# Sparkfun_MiP_ProMini-Pack.net
KiCad netlist of a schematic drawn in EAGLE
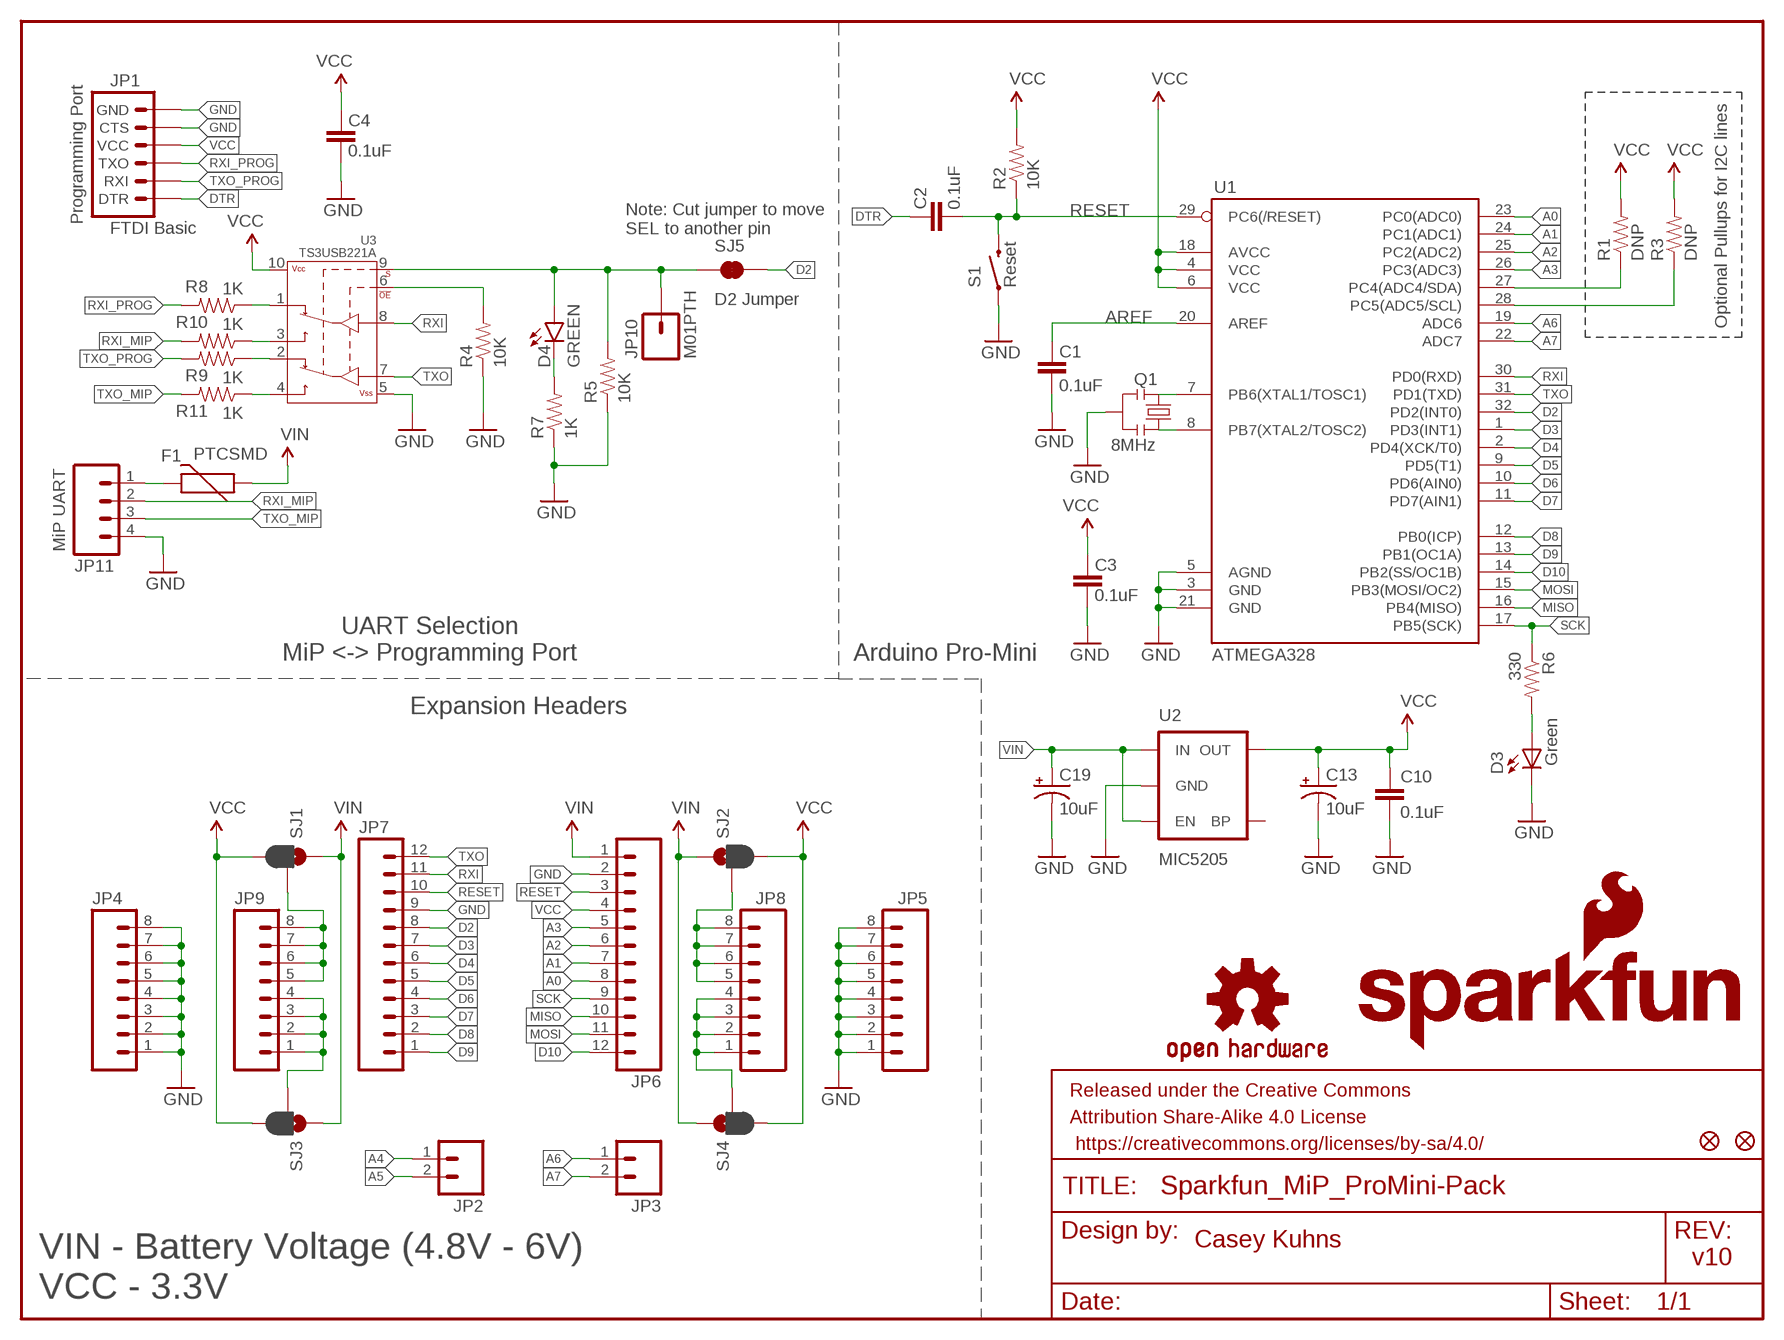
[diagram p0: schematic, sheet 1]

(export (version "E")
  (design (tool "Eeschema 10.0.6"))
  (components
    (comp (ref "C1")
      (value "0.1uF")
      (footprint "eagle-import:0603-CAP")
      (libsource (lib "eagle-import") (part "CAP0603-CAP"))
    )
    (comp (ref "C2")
      (value "0.1uF")
      (footprint "eagle-import:0603-CAP")
      (libsource (lib "eagle-import") (part "CAP0603-CAP"))
    )
    (comp (ref "C3")
      (value "0.1uF")
      (footprint "eagle-import:0603-CAP")
      (libsource (lib "eagle-import") (part "CAP0603-CAP"))
    )
    (comp (ref "C4")
      (value "0.1uF")
      (footprint "eagle-import:0603-CAP")
      (libsource (lib "eagle-import") (part "CAP0603-CAP"))
    )
    (comp (ref "C10")
      (value "0.1uF")
      (footprint "eagle-import:0603-CAP")
      (libsource (lib "eagle-import") (part "CAP0603-CAP"))
    )
    (comp (ref "C13")
      (value "10uF")
      (footprint "eagle-import:EIA3216")
      (libsource (lib "eagle-import") (part "CAP_POL1206"))
    )
    (comp (ref "C19")
      (value "10uF")
      (footprint "eagle-import:EIA3216")
      (libsource (lib "eagle-import") (part "CAP_POL1206"))
    )
    (comp (ref "D3")
      (value "Green")
      (footprint "eagle-import:0603-LED-ALT1")
      (libsource (lib "eagle-import") (part "LED"))
    )
    (comp (ref "D4")
      (value "GREEN")
      (footprint "eagle-import:LED-0603")
      (libsource (lib "eagle-import") (part "LED-GREEN0603"))
    )
    (comp (ref "F1")
      (value "PTCSMD")
      (footprint "eagle-import:PTC-1206")
      (libsource (lib "eagle-import") (part "PTCSMD"))
    )
    (comp (ref "FID1")
      (value "FIDUCIAL1X2")
      (footprint "eagle-import:FIDUCIAL-1X2")
      (libsource (lib "eagle-import") (part "FIDUCIAL1X2"))
    )
    (comp (ref "FID2")
      (value "FIDUCIAL1X2")
      (footprint "eagle-import:FIDUCIAL-1X2")
      (libsource (lib "eagle-import") (part "FIDUCIAL1X2"))
    )
    (comp (ref "FRAME1")
      (value "FRAME-LETTER")
      (footprint "eagle-import:CREATIVE_COMMONS")
      (libsource (lib "eagle-import") (part "FRAME-LETTER"))
    )
    (comp (ref "JP1")
      (value "FTDI Basic")
      (footprint "eagle-import:1X06")
      (libsource (lib "eagle-import") (part "ARDUINO_SERIAL_PROGRAMPTH"))
    )
    (comp (ref "JP2")
      (value "M02PTH")
      (footprint "eagle-import:1X02")
      (libsource (lib "eagle-import") (part "M02PTH"))
    )
    (comp (ref "JP3")
      (value "M02PTH")
      (footprint "eagle-import:1X02")
      (libsource (lib "eagle-import") (part "M02PTH"))
    )
    (comp (ref "JP4")
      (value "M081X08")
      (footprint "eagle-import:1X08")
      (libsource (lib "eagle-import") (part "M081X08"))
    )
    (comp (ref "JP5")
      (value "M081X08")
      (footprint "eagle-import:1X08")
      (libsource (lib "eagle-import") (part "M081X08"))
    )
    (comp (ref "JP6")
      (value "M12PTH")
      (footprint "eagle-import:1X12")
      (libsource (lib "eagle-import") (part "M12PTH"))
    )
    (comp (ref "JP7")
      (value "M12PTH")
      (footprint "eagle-import:1X12")
      (libsource (lib "eagle-import") (part "M12PTH"))
    )
    (comp (ref "JP8")
      (value "M081X08")
      (footprint "eagle-import:1X08")
      (libsource (lib "eagle-import") (part "M081X08"))
    )
    (comp (ref "JP9")
      (value "M081X08")
      (footprint "eagle-import:1X08")
      (libsource (lib "eagle-import") (part "M081X08"))
    )
    (comp (ref "JP10")
      (value "M01PTH")
      (footprint "eagle-import:1X01")
      (libsource (lib "eagle-import") (part "M01PTH"))
    )
    (comp (ref "JP11")
      (value "M04JST")
      (footprint "eagle-import:1X04-1.5MM_JST")
      (libsource (lib "eagle-import") (part "M04JST"))
    )
    (comp (ref "LOGO1")
      (value "SFE_LOGO_NAME_FLAME.1_INCH")
      (footprint "eagle-import:SFE_LOGO_NAME_FLAME_.1")
      (libsource (lib "eagle-import") (part "SFE_LOGO_NAME_FLAME.1_INCH"))
    )
    (comp (ref "LOGO2")
      (value "OSHW-LOGOS")
      (footprint "eagle-import:OSHW-LOGO-S")
      (libsource (lib "eagle-import") (part "OSHW-LOGOS"))
    )
    (comp (ref "Q1")
      (value "8MHz")
      (footprint "eagle-import:RESONATOR-SMD")
      (libsource (lib "eagle-import") (part "RESONATOR8MHZ"))
    )
    (comp (ref "R1")
      (value "DNP")
      (footprint "eagle-import:0603-RES")
      (libsource (lib "eagle-import") (part "RESISTOR0603-RES"))
    )
    (comp (ref "R2")
      (value "10K")
      (footprint "eagle-import:0603-RES")
      (libsource (lib "eagle-import") (part "RESISTOR0603-RES"))
    )
    (comp (ref "R3")
      (value "DNP")
      (footprint "eagle-import:0603-RES")
      (libsource (lib "eagle-import") (part "RESISTOR0603-RES"))
    )
    (comp (ref "R4")
      (value "10K")
      (footprint "eagle-import:0603-RES")
      (libsource (lib "eagle-import") (part "10KOHM1/10W1%(0603)0603"))
    )
    (comp (ref "R5")
      (value "10K")
      (footprint "eagle-import:0603-RES")
      (libsource (lib "eagle-import") (part "10KOHM1/10W1%(0603)0603"))
    )
    (comp (ref "R6")
      (value "330")
      (footprint "eagle-import:0603-RES")
      (libsource (lib "eagle-import") (part "RESISTOR0603-RES"))
    )
    (comp (ref "R7")
      (value "1K")
      (footprint "eagle-import:0603-RES")
      (libsource (lib "eagle-import") (part "1KOHM1/10W1%(0603)"))
    )
    (comp (ref "R8")
      (value "1K")
      (footprint "eagle-import:0603-RES")
      (libsource (lib "eagle-import") (part "1KOHM1/10W1%(0603)"))
    )
    (comp (ref "R9")
      (value "1K")
      (footprint "eagle-import:0603-RES")
      (libsource (lib "eagle-import") (part "1KOHM1/10W1%(0603)"))
    )
    (comp (ref "R10")
      (value "1K")
      (footprint "eagle-import:0603-RES")
      (libsource (lib "eagle-import") (part "1KOHM1/10W1%(0603)"))
    )
    (comp (ref "R11")
      (value "1K")
      (footprint "eagle-import:0603-RES")
      (libsource (lib "eagle-import") (part "1KOHM1/10W1%(0603)"))
    )
    (comp (ref "S1")
      (value "Reset")
      (footprint "eagle-import:TACTILE-SWITCH-SMD-ALT01")
      (libsource (lib "eagle-import") (part "SWITCH-MOMENTARY-2SMD-ALT01"))
    )
    (comp (ref "SJ1")
      (value "JUMPER-PAD-3-2OF3_NC_BY_PASTE")
      (footprint "eagle-import:PAD-JUMPER-3-2OF3_NC_BY_PASTE_YES_SILK_FULL_BOX")
      (libsource (lib "eagle-import") (part "JUMPER-PAD-3-2OF3_NC_BY_PASTE"))
    )
    (comp (ref "SJ2")
      (value "JUMPER-PAD-3-2OF3_NC_BY_PASTE")
      (footprint "eagle-import:PAD-JUMPER-3-2OF3_NC_BY_PASTE_YES_SILK_FULL_BOX")
      (libsource (lib "eagle-import") (part "JUMPER-PAD-3-2OF3_NC_BY_PASTE"))
    )
    (comp (ref "SJ3")
      (value "JUMPER-PAD-3-2OF3_NC_BY_PASTE")
      (footprint "eagle-import:PAD-JUMPER-3-2OF3_NC_BY_PASTE_YES_SILK_FULL_BOX")
      (libsource (lib "eagle-import") (part "JUMPER-PAD-3-2OF3_NC_BY_PASTE"))
    )
    (comp (ref "SJ4")
      (value "JUMPER-PAD-3-2OF3_NC_BY_PASTE")
      (footprint "eagle-import:PAD-JUMPER-3-2OF3_NC_BY_PASTE_YES_SILK_FULL_BOX")
      (libsource (lib "eagle-import") (part "JUMPER-PAD-3-2OF3_NC_BY_PASTE"))
    )
    (comp (ref "SJ5")
      (value "D2 Jumper")
      (footprint "eagle-import:PAD-JUMPER-2-NC_BY_TRACE_YES_SILK")
      (libsource (lib "eagle-import") (part "JUMPER-PAD-2-NC_BY_TRACE"))
    )
    (comp (ref "U1")
      (value "ATMEGA328")
      (footprint "eagle-import:TQFP32-08")
      (libsource (lib "eagle-import") (part "ATMEGA168"))
    )
    (comp (ref "U2")
      (value "MIC5205")
      (footprint "eagle-import:SOT23-5")
      (libsource (lib "eagle-import") (part "V_REG_LDOSMD"))
    )
    (comp (ref "U3")
      (value "TS3USB221A")
      (footprint "eagle-import:QFN-10-RSE")
      (libsource (lib "eagle-import") (part "TS3USB221A"))
    )
  )
  (nets
    (net (code "1") (name "/AREF") (class "Default")
      (node (ref "C1") (pin "2") (pinfunction "2_2") (pintype "passive"))
      (node (ref "U1") (pin "20") (pinfunction "AREF_20") (pintype "bidirectional"))
    )
    (net (code "2") (name "A0") (class "Default")
      (node (ref "JP6") (pin "8") (pinfunction "8_8") (pintype "passive"))
      (node (ref "U1") (pin "23") (pinfunction "PC0(ADC0)_23") (pintype "bidirectional"))
    )
    (net (code "3") (name "A1") (class "Default")
      (node (ref "JP6") (pin "7") (pinfunction "7_7") (pintype "passive"))
      (node (ref "U1") (pin "24") (pinfunction "PC1(ADC1)_24") (pintype "bidirectional"))
    )
    (net (code "4") (name "A2") (class "Default")
      (node (ref "JP6") (pin "6") (pinfunction "6_6") (pintype "passive"))
      (node (ref "U1") (pin "25") (pinfunction "PC2(ADC2)_25") (pintype "bidirectional"))
    )
    (net (code "5") (name "A3") (class "Default")
      (node (ref "JP6") (pin "5") (pinfunction "5_5") (pintype "passive"))
      (node (ref "U1") (pin "26") (pinfunction "PC3(ADC3)_26") (pintype "bidirectional"))
    )
    (net (code "6") (name "A4") (class "Default")
      (node (ref "JP2") (pin "1") (pinfunction "1_1") (pintype "passive"))
      (node (ref "R1") (pin "1") (pinfunction "1_1") (pintype "passive"))
      (node (ref "U1") (pin "27") (pinfunction "PC4(ADC4/SDA)_27") (pintype "bidirectional"))
    )
    (net (code "7") (name "A5") (class "Default")
      (node (ref "JP2") (pin "2") (pinfunction "2_2") (pintype "passive"))
      (node (ref "R3") (pin "1") (pinfunction "1_1") (pintype "passive"))
      (node (ref "U1") (pin "28") (pinfunction "PC5(ADC5/SCL)_28") (pintype "bidirectional"))
    )
    (net (code "8") (name "A6") (class "Default")
      (node (ref "JP3") (pin "1") (pinfunction "1_1") (pintype "passive"))
      (node (ref "U1") (pin "19") (pinfunction "ADC6_19") (pintype "bidirectional"))
    )
    (net (code "9") (name "A7") (class "Default")
      (node (ref "JP3") (pin "2") (pinfunction "2_2") (pintype "passive"))
      (node (ref "U1") (pin "22") (pinfunction "ADC7_22") (pintype "bidirectional"))
    )
    (net (code "10") (name "D2") (class "Default")
      (node (ref "JP7") (pin "8") (pinfunction "8_8") (pintype "passive"))
      (node (ref "SJ5") (pin "2") (pinfunction "2_2") (pintype "passive"))
      (node (ref "U1") (pin "32") (pinfunction "PD2(INT0)_32") (pintype "bidirectional"))
    )
    (net (code "11") (name "D3") (class "Default")
      (node (ref "JP7") (pin "7") (pinfunction "7_7") (pintype "passive"))
      (node (ref "U1") (pin "1") (pinfunction "PD3(INT1)_1") (pintype "bidirectional"))
    )
    (net (code "12") (name "D4") (class "Default")
      (node (ref "JP7") (pin "6") (pinfunction "6_6") (pintype "passive"))
      (node (ref "U1") (pin "2") (pinfunction "PD4(XCK/T0)_2") (pintype "bidirectional"))
    )
    (net (code "13") (name "D5") (class "Default")
      (node (ref "JP7") (pin "5") (pinfunction "5_5") (pintype "passive"))
      (node (ref "U1") (pin "9") (pinfunction "PD5(T1)_9") (pintype "bidirectional"))
    )
    (net (code "14") (name "D6") (class "Default")
      (node (ref "JP7") (pin "4") (pinfunction "4_4") (pintype "passive"))
      (node (ref "U1") (pin "10") (pinfunction "PD6(AIN0)_10") (pintype "bidirectional"))
    )
    (net (code "15") (name "D7") (class "Default")
      (node (ref "JP7") (pin "3") (pinfunction "3_3") (pintype "passive"))
      (node (ref "U1") (pin "11") (pinfunction "PD7(AIN1)_11") (pintype "bidirectional"))
    )
    (net (code "16") (name "D8") (class "Default")
      (node (ref "JP7") (pin "2") (pinfunction "2_2") (pintype "passive"))
      (node (ref "U1") (pin "12") (pinfunction "PB0(ICP)_12") (pintype "bidirectional"))
    )
    (net (code "17") (name "D9") (class "Default")
      (node (ref "JP7") (pin "1") (pinfunction "1_1") (pintype "passive"))
      (node (ref "U1") (pin "13") (pinfunction "PB1(OC1A)_13") (pintype "bidirectional"))
    )
    (net (code "18") (name "D10") (class "Default")
      (node (ref "JP6") (pin "12") (pinfunction "12_12") (pintype "passive"))
      (node (ref "U1") (pin "14") (pinfunction "PB2(SS/OC1B)_14") (pintype "bidirectional"))
    )
    (net (code "19") (name "DTR") (class "Default")
      (node (ref "C2") (pin "2") (pinfunction "2_2") (pintype "passive"))
      (node (ref "JP1") (pin "1") (pinfunction "DTR_1") (pintype "passive"))
    )
    (net (code "20") (name "GND") (class "Default")
      (node (ref "C1") (pin "1") (pinfunction "1_1") (pintype "passive"))
      (node (ref "C10") (pin "2") (pinfunction "2_2") (pintype "passive"))
      (node (ref "C13") (pin "C") (pinfunction "-_C") (pintype "passive"))
      (node (ref "C19") (pin "C") (pinfunction "-_C") (pintype "passive"))
      (node (ref "C3") (pin "1") (pinfunction "1_1") (pintype "passive"))
      (node (ref "C4") (pin "1") (pinfunction "1_1") (pintype "passive"))
      (node (ref "D3") (pin "C") (pinfunction "C_C") (pintype "passive"))
      (node (ref "JP1") (pin "5") (pinfunction "CTS_5") (pintype "passive"))
      (node (ref "JP1") (pin "6") (pinfunction "GND_6") (pintype "passive"))
      (node (ref "JP11") (pin "4") (pinfunction "4_4") (pintype "passive"))
      (node (ref "JP4") (pin "1") (pinfunction "1_1") (pintype "passive"))
      (node (ref "JP4") (pin "2") (pinfunction "2_2") (pintype "passive"))
      (node (ref "JP4") (pin "3") (pinfunction "3_3") (pintype "passive"))
      (node (ref "JP4") (pin "4") (pinfunction "4_4") (pintype "passive"))
      (node (ref "JP4") (pin "5") (pinfunction "5_5") (pintype "passive"))
      (node (ref "JP4") (pin "6") (pinfunction "6_6") (pintype "passive"))
      (node (ref "JP4") (pin "7") (pinfunction "7_7") (pintype "passive"))
      (node (ref "JP4") (pin "8") (pinfunction "8_8") (pintype "passive"))
      (node (ref "JP5") (pin "1") (pinfunction "1_1") (pintype "passive"))
      (node (ref "JP5") (pin "2") (pinfunction "2_2") (pintype "passive"))
      (node (ref "JP5") (pin "3") (pinfunction "3_3") (pintype "passive"))
      (node (ref "JP5") (pin "4") (pinfunction "4_4") (pintype "passive"))
      (node (ref "JP5") (pin "5") (pinfunction "5_5") (pintype "passive"))
      (node (ref "JP5") (pin "6") (pinfunction "6_6") (pintype "passive"))
      (node (ref "JP5") (pin "7") (pinfunction "7_7") (pintype "passive"))
      (node (ref "JP5") (pin "8") (pinfunction "8_8") (pintype "passive"))
      (node (ref "JP6") (pin "2") (pinfunction "2_2") (pintype "passive"))
      (node (ref "JP7") (pin "9") (pinfunction "9_9") (pintype "passive"))
      (node (ref "Q1") (pin "2") (pinfunction "2_2") (pintype "passive"))
      (node (ref "R4") (pin "1") (pinfunction "1_1") (pintype "passive"))
      (node (ref "R5") (pin "1") (pinfunction "1_1") (pintype "passive"))
      (node (ref "R7") (pin "1") (pinfunction "1_1") (pintype "passive"))
      (node (ref "S1") (pin "1") (pinfunction "1_1") (pintype "passive"))
      (node (ref "S1") (pin "2") (pinfunction "1_2") (pintype "passive"))
      (node (ref "U1") (pin "21") (pinfunction "GND_21") (pintype "bidirectional"))
      (node (ref "U1") (pin "3") (pinfunction "GND_3") (pintype "bidirectional"))
      (node (ref "U1") (pin "5") (pinfunction "AGND_5") (pintype "bidirectional"))
      (node (ref "U2") (pin "2") (pinfunction "GND_2") (pintype "input"))
      (node (ref "U3") (pin "5") (pinfunction "VSS_5") (pintype "bidirectional"))
    )
    (net (code "21") (name "MISO") (class "Default")
      (node (ref "JP6") (pin "10") (pinfunction "10_10") (pintype "passive"))
      (node (ref "U1") (pin "16") (pinfunction "PB4(MISO)_16") (pintype "bidirectional"))
    )
    (net (code "22") (name "MOSI") (class "Default")
      (node (ref "JP6") (pin "11") (pinfunction "11_11") (pintype "passive"))
      (node (ref "U1") (pin "15") (pinfunction "PB3(MOSI/OC2)_15") (pintype "bidirectional"))
    )
    (net (code "23") (name "Net-(D3-PadA)") (class "Default")
      (node (ref "D3") (pin "A") (pinfunction "A_A") (pintype "passive"))
      (node (ref "R6") (pin "2") (pinfunction "2_2") (pintype "passive"))
    )
    (net (code "24") (name "Net-(D4-PadC)") (class "Default")
      (node (ref "D4") (pin "C") (pinfunction "C_C") (pintype "passive"))
      (node (ref "R7") (pin "2") (pinfunction "2_2") (pintype "passive"))
    )
    (net (code "25") (name "Net-(F1-Pad2)") (class "Default")
      (node (ref "F1") (pin "2") (pinfunction "2_2") (pintype "bidirectional"))
      (node (ref "JP11") (pin "1") (pinfunction "1_1") (pintype "passive"))
    )
    (net (code "26") (name "Net-(JP8-Pad1)") (class "Default")
      (node (ref "JP8") (pin "1") (pinfunction "1_1") (pintype "passive"))
      (node (ref "JP8") (pin "2") (pinfunction "2_2") (pintype "passive"))
      (node (ref "JP8") (pin "3") (pinfunction "3_3") (pintype "passive"))
      (node (ref "JP8") (pin "4") (pinfunction "4_4") (pintype "passive"))
      (node (ref "SJ4") (pin "2") (pinfunction "2_2") (pintype "passive"))
    )
    (net (code "27") (name "Net-(JP8-Pad5)") (class "Default")
      (node (ref "JP8") (pin "5") (pinfunction "5_5") (pintype "passive"))
      (node (ref "JP8") (pin "6") (pinfunction "6_6") (pintype "passive"))
      (node (ref "JP8") (pin "7") (pinfunction "7_7") (pintype "passive"))
      (node (ref "JP8") (pin "8") (pinfunction "8_8") (pintype "passive"))
      (node (ref "SJ2") (pin "2") (pinfunction "2_2") (pintype "passive"))
    )
    (net (code "28") (name "Net-(JP9-Pad1)") (class "Default")
      (node (ref "JP9") (pin "1") (pinfunction "1_1") (pintype "passive"))
      (node (ref "JP9") (pin "2") (pinfunction "2_2") (pintype "passive"))
      (node (ref "JP9") (pin "3") (pinfunction "3_3") (pintype "passive"))
      (node (ref "JP9") (pin "4") (pinfunction "4_4") (pintype "passive"))
      (node (ref "SJ3") (pin "2") (pinfunction "2_2") (pintype "passive"))
    )
    (net (code "29") (name "Net-(JP9-Pad5)") (class "Default")
      (node (ref "JP9") (pin "5") (pinfunction "5_5") (pintype "passive"))
      (node (ref "JP9") (pin "6") (pinfunction "6_6") (pintype "passive"))
      (node (ref "JP9") (pin "7") (pinfunction "7_7") (pintype "passive"))
      (node (ref "JP9") (pin "8") (pinfunction "8_8") (pintype "passive"))
      (node (ref "SJ1") (pin "2") (pinfunction "2_2") (pintype "passive"))
    )
    (net (code "30") (name "Net-(U1-PB6(XTAL1{slash}TOSC1))") (class "Default")
      (node (ref "Q1") (pin "1") (pinfunction "1_1") (pintype "passive"))
      (node (ref "U1") (pin "7") (pinfunction "PB6(XTAL1/TOSC1)_7") (pintype "bidirectional"))
    )
    (net (code "31") (name "Net-(U1-PB7(XTAL2{slash}TOSC2))") (class "Default")
      (node (ref "Q1") (pin "3") (pinfunction "3_3") (pintype "passive"))
      (node (ref "U1") (pin "8") (pinfunction "PB7(XTAL2/TOSC2)_8") (pintype "bidirectional"))
    )
    (net (code "32") (name "Net-(U3-1D+)") (class "Default")
      (node (ref "R8") (pin "1") (pinfunction "1_1") (pintype "passive"))
      (node (ref "U3") (pin "1") (pinfunction "1D+_1") (pintype "bidirectional"))
    )
    (net (code "33") (name "Net-(U3-1D-)") (class "Default")
      (node (ref "R9") (pin "1") (pinfunction "1_1") (pintype "passive"))
      (node (ref "U3") (pin "2") (pinfunction "1D-_2") (pintype "bidirectional"))
    )
    (net (code "34") (name "Net-(U3-2D+)") (class "Default")
      (node (ref "R10") (pin "1") (pinfunction "1_1") (pintype "passive"))
      (node (ref "U3") (pin "3") (pinfunction "2D+_3") (pintype "bidirectional"))
    )
    (net (code "35") (name "Net-(U3-2D-)") (class "Default")
      (node (ref "R11") (pin "1") (pinfunction "1_1") (pintype "passive"))
      (node (ref "U3") (pin "4") (pinfunction "2D-_4") (pintype "bidirectional"))
    )
    (net (code "36") (name "Net-(U3-S)") (class "Default")
      (node (ref "D4") (pin "A") (pinfunction "A_A") (pintype "passive"))
      (node (ref "JP10") (pin "1") (pinfunction "1_1") (pintype "passive"))
      (node (ref "R5") (pin "2") (pinfunction "2_2") (pintype "passive"))
      (node (ref "SJ5") (pin "1") (pinfunction "1_1") (pintype "passive"))
      (node (ref "U3") (pin "9") (pinfunction "S_9") (pintype "bidirectional"))
    )
    (net (code "37") (name "Net-(U3-~{OE})") (class "Default")
      (node (ref "R4") (pin "2") (pinfunction "2_2") (pintype "passive"))
      (node (ref "U3") (pin "6") (pinfunction "~{OE}_6") (pintype "bidirectional"))
    )
    (net (code "38") (name "RESET") (class "Default")
      (node (ref "C2") (pin "1") (pinfunction "1_1") (pintype "passive"))
      (node (ref "JP6") (pin "3") (pinfunction "3_3") (pintype "passive"))
      (node (ref "JP7") (pin "10") (pinfunction "10_10") (pintype "passive"))
      (node (ref "R2") (pin "1") (pinfunction "1_1") (pintype "passive"))
      (node (ref "S1") (pin "3") (pinfunction "2_3") (pintype "passive"))
      (node (ref "S1") (pin "4") (pinfunction "2_4") (pintype "passive"))
      (node (ref "U1") (pin "29") (pinfunction "PC6(/RESET)_29") (pintype "bidirectional"))
    )
    (net (code "39") (name "RXI") (class "Default")
      (node (ref "JP7") (pin "11") (pinfunction "11_11") (pintype "passive"))
      (node (ref "U1") (pin "30") (pinfunction "PD0(RXD)_30") (pintype "bidirectional"))
      (node (ref "U3") (pin "8") (pinfunction "D+_8") (pintype "bidirectional"))
    )
    (net (code "40") (name "RXI_MIP") (class "Default")
      (node (ref "JP11") (pin "2") (pinfunction "2_2") (pintype "passive"))
      (node (ref "R10") (pin "2") (pinfunction "2_2") (pintype "passive"))
    )
    (net (code "41") (name "RXI_PROG") (class "Default")
      (node (ref "JP1") (pin "3") (pinfunction "TXO_3") (pintype "passive"))
      (node (ref "R8") (pin "2") (pinfunction "2_2") (pintype "passive"))
    )
    (net (code "42") (name "SCK") (class "Default")
      (node (ref "JP6") (pin "9") (pinfunction "9_9") (pintype "passive"))
      (node (ref "R6") (pin "1") (pinfunction "1_1") (pintype "passive"))
      (node (ref "U1") (pin "17") (pinfunction "PB5(SCK)_17") (pintype "bidirectional"))
    )
    (net (code "43") (name "TXO") (class "Default")
      (node (ref "JP7") (pin "12") (pinfunction "12_12") (pintype "passive"))
      (node (ref "U1") (pin "31") (pinfunction "PD1(TXD)_31") (pintype "bidirectional"))
      (node (ref "U3") (pin "7") (pinfunction "D-_7") (pintype "bidirectional"))
    )
    (net (code "44") (name "TXO_MIP") (class "Default")
      (node (ref "JP11") (pin "3") (pinfunction "3_3") (pintype "passive"))
      (node (ref "R11") (pin "2") (pinfunction "2_2") (pintype "passive"))
    )
    (net (code "45") (name "TXO_PROG") (class "Default")
      (node (ref "JP1") (pin "2") (pinfunction "RXI_2") (pintype "passive"))
      (node (ref "R9") (pin "2") (pinfunction "2_2") (pintype "passive"))
    )
    (net (code "46") (name "VCC") (class "Default")
      (node (ref "C10") (pin "1") (pinfunction "1_1") (pintype "passive"))
      (node (ref "C13") (pin "A") (pinfunction "+_A") (pintype "passive"))
      (node (ref "C3") (pin "2") (pinfunction "2_2") (pintype "passive"))
      (node (ref "C4") (pin "2") (pinfunction "2_2") (pintype "passive"))
      (node (ref "JP1") (pin "4") (pinfunction "VCC_4") (pintype "passive"))
      (node (ref "JP6") (pin "4") (pinfunction "4_4") (pintype "passive"))
      (node (ref "R1") (pin "2") (pinfunction "2_2") (pintype "passive"))
      (node (ref "R2") (pin "2") (pinfunction "2_2") (pintype "passive"))
      (node (ref "R3") (pin "2") (pinfunction "2_2") (pintype "passive"))
      (node (ref "SJ1") (pin "3") (pinfunction "3_3") (pintype "passive"))
      (node (ref "SJ2") (pin "3") (pinfunction "3_3") (pintype "passive"))
      (node (ref "SJ3") (pin "3") (pinfunction "3_3") (pintype "passive"))
      (node (ref "SJ4") (pin "3") (pinfunction "3_3") (pintype "passive"))
      (node (ref "U1") (pin "18") (pinfunction "AVCC_18") (pintype "bidirectional"))
      (node (ref "U1") (pin "4") (pinfunction "VCC_4") (pintype "bidirectional"))
      (node (ref "U1") (pin "6") (pinfunction "VCC_6") (pintype "bidirectional"))
      (node (ref "U2") (pin "5") (pinfunction "OUT_5") (pintype "passive"))
      (node (ref "U3") (pin "10") (pinfunction "VCC_10") (pintype "bidirectional"))
    )
    (net (code "47") (name "VIN") (class "Default")
      (node (ref "C19") (pin "A") (pinfunction "+_A") (pintype "passive"))
      (node (ref "F1") (pin "1") (pinfunction "1_1") (pintype "bidirectional"))
      (node (ref "JP6") (pin "1") (pinfunction "1_1") (pintype "passive"))
      (node (ref "SJ1") (pin "1") (pinfunction "1_1") (pintype "passive"))
      (node (ref "SJ2") (pin "1") (pinfunction "1_1") (pintype "passive"))
      (node (ref "SJ3") (pin "1") (pinfunction "1_1") (pintype "passive"))
      (node (ref "SJ4") (pin "1") (pinfunction "1_1") (pintype "passive"))
      (node (ref "U2") (pin "1") (pinfunction "IN_1") (pintype "input"))
      (node (ref "U2") (pin "3") (pinfunction "EN_3") (pintype "input"))
    )
    (net (code "48") (name "unconnected-(U2-BP-Pad4)") (class "Default")
      (node (ref "U2") (pin "4") (pinfunction "BP_4") (pintype "input"))
    )
  )
)
